# 4_waffling60-NMB_periferals.net
KiCad netlist of a schematic drawn in Altium Designer
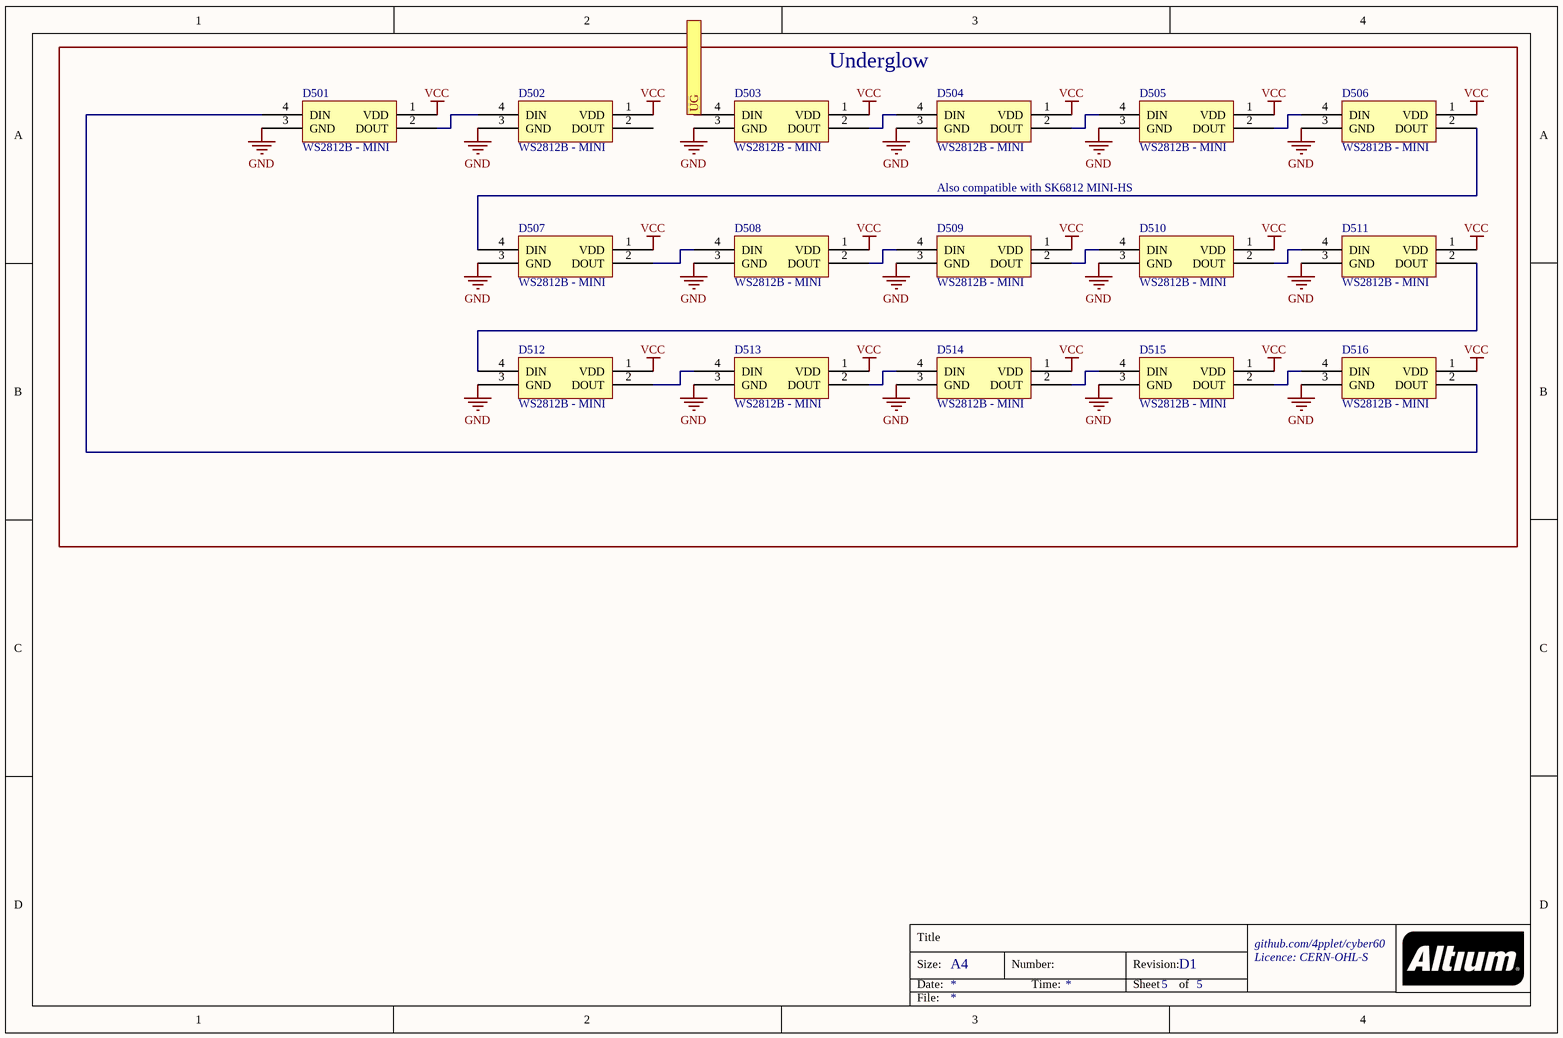
[diagram p0: 4_waffling60-NMB_periferals.SchDoc]

(export (version "E")
  (design (tool "Eeschema 10.0.6"))
  (components
    (comp (ref "D501")
      (value "WS2812B - MINI")
      (footprint "WS2812B - 2020")
      (fields (field (name "LCSC PART #") "C965556") (field (name "MRF.PART") "WS2812C-2020"))
      (libsource (lib "Keebs") (part "WS2812B"))
    )
    (comp (ref "D502")
      (value "WS2812B - MINI")
      (footprint "WS2812B - 2020")
      (fields (field (name "LCSC PART #") "C965556") (field (name "MRF.PART") "WS2812C-2020"))
      (libsource (lib "Keebs") (part "WS2812B"))
    )
    (comp (ref "D503")
      (value "WS2812B - MINI")
      (footprint "WS2812B - 2020")
      (fields (field (name "LCSC PART #") "C965556") (field (name "MRF.PART") "WS2812C-2020"))
      (libsource (lib "Keebs") (part "WS2812B"))
    )
    (comp (ref "D504")
      (value "WS2812B - MINI")
      (footprint "WS2812B - 2020")
      (fields (field (name "LCSC PART #") "C965556") (field (name "MRF.PART") "WS2812C-2020"))
      (libsource (lib "Keebs") (part "WS2812B"))
    )
    (comp (ref "D505")
      (value "WS2812B - MINI")
      (footprint "WS2812B - 2020")
      (fields (field (name "LCSC PART #") "C965556") (field (name "MRF.PART") "WS2812C-2020"))
      (libsource (lib "Keebs") (part "WS2812B"))
    )
    (comp (ref "D506")
      (value "WS2812B - MINI")
      (footprint "WS2812B - 2020")
      (fields (field (name "LCSC PART #") "C965556") (field (name "MRF.PART") "WS2812C-2020"))
      (libsource (lib "Keebs") (part "WS2812B"))
    )
    (comp (ref "D507")
      (value "WS2812B - MINI")
      (footprint "WS2812B - 2020")
      (fields (field (name "LCSC PART #") "C965556") (field (name "MRF.PART") "WS2812C-2020"))
      (libsource (lib "Keebs") (part "WS2812B"))
    )
    (comp (ref "D508")
      (value "WS2812B - MINI")
      (footprint "WS2812B - 2020")
      (fields (field (name "LCSC PART #") "C965556") (field (name "MRF.PART") "WS2812C-2020"))
      (libsource (lib "Keebs") (part "WS2812B"))
    )
    (comp (ref "D509")
      (value "WS2812B - MINI")
      (footprint "WS2812B - 2020")
      (fields (field (name "LCSC PART #") "C965556") (field (name "MRF.PART") "WS2812C-2020"))
      (libsource (lib "Keebs") (part "WS2812B"))
    )
    (comp (ref "D510")
      (value "WS2812B - MINI")
      (footprint "WS2812B - 2020")
      (fields (field (name "LCSC PART #") "C965556") (field (name "MRF.PART") "WS2812C-2020"))
      (libsource (lib "Keebs") (part "WS2812B"))
    )
    (comp (ref "D511")
      (value "WS2812B - MINI")
      (footprint "WS2812B - 2020")
      (fields (field (name "LCSC PART #") "C965556") (field (name "MRF.PART") "WS2812C-2020"))
      (libsource (lib "Keebs") (part "WS2812B"))
    )
    (comp (ref "D512")
      (value "WS2812B - MINI")
      (footprint "WS2812B - 2020")
      (fields (field (name "LCSC PART #") "C965556") (field (name "MRF.PART") "WS2812C-2020"))
      (libsource (lib "Keebs") (part "WS2812B"))
    )
    (comp (ref "D513")
      (value "WS2812B - MINI")
      (footprint "WS2812B - 2020")
      (fields (field (name "LCSC PART #") "C965556") (field (name "MRF.PART") "WS2812C-2020"))
      (libsource (lib "Keebs") (part "WS2812B"))
    )
    (comp (ref "D514")
      (value "WS2812B - MINI")
      (footprint "WS2812B - 2020")
      (fields (field (name "LCSC PART #") "C965556") (field (name "MRF.PART") "WS2812C-2020"))
      (libsource (lib "Keebs") (part "WS2812B"))
    )
    (comp (ref "D515")
      (value "WS2812B - MINI")
      (footprint "WS2812B - 2020")
      (fields (field (name "LCSC PART #") "C965556") (field (name "MRF.PART") "WS2812C-2020"))
      (libsource (lib "Keebs") (part "WS2812B"))
    )
    (comp (ref "D516")
      (value "WS2812B - MINI")
      (footprint "WS2812B - 2020")
      (fields (field (name "LCSC PART #") "C965556") (field (name "MRF.PART") "WS2812C-2020"))
      (libsource (lib "Keebs") (part "WS2812B"))
    )
  )
  (nets
    (net (code "1") (name "/UG") (class "Default")
      (node (ref "D503") (pin "4") (pinfunction "DIN_4") (pintype "passive"))
    )
    (net (code "2") (name "GND") (class "Default")
      (node (ref "D501") (pin "3") (pinfunction "GND_3") (pintype "passive"))
      (node (ref "D502") (pin "3") (pinfunction "GND_3") (pintype "passive"))
      (node (ref "D503") (pin "3") (pinfunction "GND_3") (pintype "passive"))
      (node (ref "D504") (pin "3") (pinfunction "GND_3") (pintype "passive"))
      (node (ref "D505") (pin "3") (pinfunction "GND_3") (pintype "passive"))
      (node (ref "D506") (pin "3") (pinfunction "GND_3") (pintype "passive"))
      (node (ref "D507") (pin "3") (pinfunction "GND_3") (pintype "passive"))
      (node (ref "D508") (pin "3") (pinfunction "GND_3") (pintype "passive"))
      (node (ref "D509") (pin "3") (pinfunction "GND_3") (pintype "passive"))
      (node (ref "D510") (pin "3") (pinfunction "GND_3") (pintype "passive"))
      (node (ref "D511") (pin "3") (pinfunction "GND_3") (pintype "passive"))
      (node (ref "D512") (pin "3") (pinfunction "GND_3") (pintype "passive"))
      (node (ref "D513") (pin "3") (pinfunction "GND_3") (pintype "passive"))
      (node (ref "D514") (pin "3") (pinfunction "GND_3") (pintype "passive"))
      (node (ref "D515") (pin "3") (pinfunction "GND_3") (pintype "passive"))
      (node (ref "D516") (pin "3") (pinfunction "GND_3") (pintype "passive"))
    )
    (net (code "3") (name "Net-(D501-DIN)") (class "Default")
      (node (ref "D501") (pin "4") (pinfunction "DIN_4") (pintype "passive"))
      (node (ref "D516") (pin "2") (pinfunction "DOUT_2") (pintype "passive"))
    )
    (net (code "4") (name "Net-(D501-DOUT)") (class "Default")
      (node (ref "D501") (pin "2") (pinfunction "DOUT_2") (pintype "passive"))
      (node (ref "D502") (pin "4") (pinfunction "DIN_4") (pintype "passive"))
    )
    (net (code "5") (name "Net-(D503-DOUT)") (class "Default")
      (node (ref "D503") (pin "2") (pinfunction "DOUT_2") (pintype "passive"))
      (node (ref "D504") (pin "4") (pinfunction "DIN_4") (pintype "passive"))
    )
    (net (code "6") (name "Net-(D504-DOUT)") (class "Default")
      (node (ref "D504") (pin "2") (pinfunction "DOUT_2") (pintype "passive"))
      (node (ref "D505") (pin "4") (pinfunction "DIN_4") (pintype "passive"))
    )
    (net (code "7") (name "Net-(D505-DOUT)") (class "Default")
      (node (ref "D505") (pin "2") (pinfunction "DOUT_2") (pintype "passive"))
      (node (ref "D506") (pin "4") (pinfunction "DIN_4") (pintype "passive"))
    )
    (net (code "8") (name "Net-(D506-DOUT)") (class "Default")
      (node (ref "D506") (pin "2") (pinfunction "DOUT_2") (pintype "passive"))
      (node (ref "D507") (pin "4") (pinfunction "DIN_4") (pintype "passive"))
    )
    (net (code "9") (name "Net-(D507-DOUT)") (class "Default")
      (node (ref "D507") (pin "2") (pinfunction "DOUT_2") (pintype "passive"))
      (node (ref "D508") (pin "4") (pinfunction "DIN_4") (pintype "passive"))
    )
    (net (code "10") (name "Net-(D508-DOUT)") (class "Default")
      (node (ref "D508") (pin "2") (pinfunction "DOUT_2") (pintype "passive"))
      (node (ref "D509") (pin "4") (pinfunction "DIN_4") (pintype "passive"))
    )
    (net (code "11") (name "Net-(D509-DOUT)") (class "Default")
      (node (ref "D509") (pin "2") (pinfunction "DOUT_2") (pintype "passive"))
      (node (ref "D510") (pin "4") (pinfunction "DIN_4") (pintype "passive"))
    )
    (net (code "12") (name "Net-(D510-DOUT)") (class "Default")
      (node (ref "D510") (pin "2") (pinfunction "DOUT_2") (pintype "passive"))
      (node (ref "D511") (pin "4") (pinfunction "DIN_4") (pintype "passive"))
    )
    (net (code "13") (name "Net-(D511-DOUT)") (class "Default")
      (node (ref "D511") (pin "2") (pinfunction "DOUT_2") (pintype "passive"))
      (node (ref "D512") (pin "4") (pinfunction "DIN_4") (pintype "passive"))
    )
    (net (code "14") (name "Net-(D512-DOUT)") (class "Default")
      (node (ref "D512") (pin "2") (pinfunction "DOUT_2") (pintype "passive"))
      (node (ref "D513") (pin "4") (pinfunction "DIN_4") (pintype "passive"))
    )
    (net (code "15") (name "Net-(D513-DOUT)") (class "Default")
      (node (ref "D513") (pin "2") (pinfunction "DOUT_2") (pintype "passive"))
      (node (ref "D514") (pin "4") (pinfunction "DIN_4") (pintype "passive"))
    )
    (net (code "16") (name "Net-(D514-DOUT)") (class "Default")
      (node (ref "D514") (pin "2") (pinfunction "DOUT_2") (pintype "passive"))
      (node (ref "D515") (pin "4") (pinfunction "DIN_4") (pintype "passive"))
    )
    (net (code "17") (name "Net-(D515-DOUT)") (class "Default")
      (node (ref "D515") (pin "2") (pinfunction "DOUT_2") (pintype "passive"))
      (node (ref "D516") (pin "4") (pinfunction "DIN_4") (pintype "passive"))
    )
    (net (code "18") (name "VCC") (class "Default")
      (node (ref "D501") (pin "1") (pinfunction "VDD_1") (pintype "passive"))
      (node (ref "D502") (pin "1") (pinfunction "VDD_1") (pintype "passive"))
      (node (ref "D503") (pin "1") (pinfunction "VDD_1") (pintype "passive"))
      (node (ref "D504") (pin "1") (pinfunction "VDD_1") (pintype "passive"))
      (node (ref "D505") (pin "1") (pinfunction "VDD_1") (pintype "passive"))
      (node (ref "D506") (pin "1") (pinfunction "VDD_1") (pintype "passive"))
      (node (ref "D507") (pin "1") (pinfunction "VDD_1") (pintype "passive"))
      (node (ref "D508") (pin "1") (pinfunction "VDD_1") (pintype "passive"))
      (node (ref "D509") (pin "1") (pinfunction "VDD_1") (pintype "passive"))
      (node (ref "D510") (pin "1") (pinfunction "VDD_1") (pintype "passive"))
      (node (ref "D511") (pin "1") (pinfunction "VDD_1") (pintype "passive"))
      (node (ref "D512") (pin "1") (pinfunction "VDD_1") (pintype "passive"))
      (node (ref "D513") (pin "1") (pinfunction "VDD_1") (pintype "passive"))
      (node (ref "D514") (pin "1") (pinfunction "VDD_1") (pintype "passive"))
      (node (ref "D515") (pin "1") (pinfunction "VDD_1") (pintype "passive"))
      (node (ref "D516") (pin "1") (pinfunction "VDD_1") (pintype "passive"))
    )
    (net (code "19") (name "unconnected-(D502-DOUT-Pad2)") (class "Default")
      (node (ref "D502") (pin "2") (pinfunction "DOUT_2") (pintype "passive"))
    )
  )
)
